# breakout.net
KiCad netlist of a schematic drawn in EAGLE
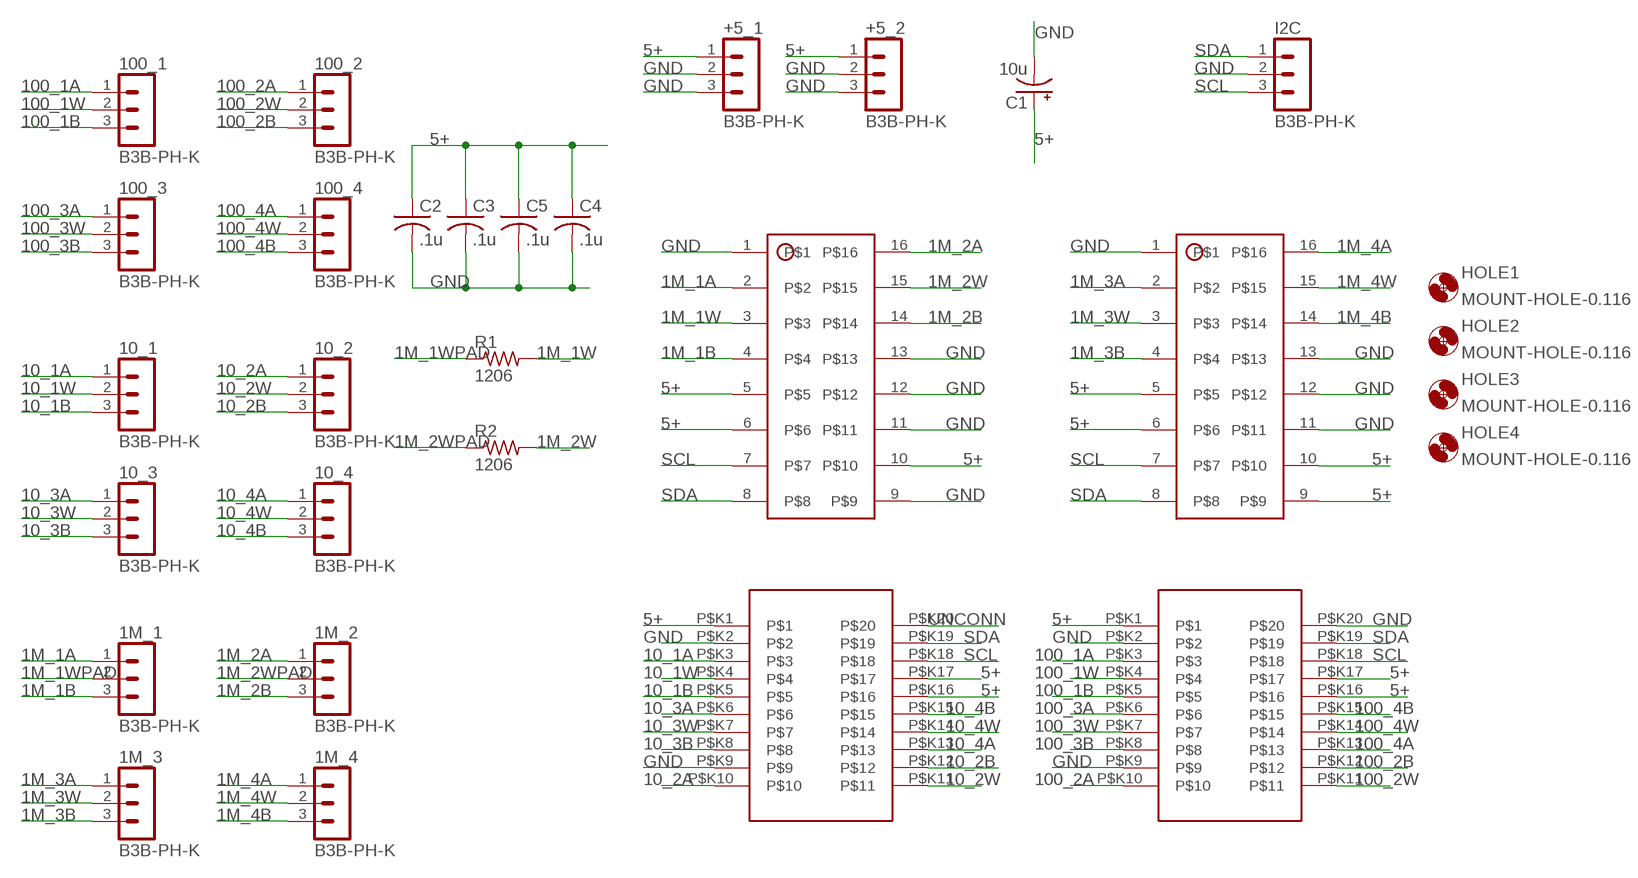
[diagram p0: schematic, sheet 1]

(export (version "E")
  (design (tool "Eeschema 10.0.6"))
  (components
    (comp (ref "+5_1")
      (value "B3B-PH-K")
      (footprint "eagle-import:B3B-PH-K")
      (libsource (lib "eagle-import") (part "B3B-PH-K"))
    )
    (comp (ref "+5_2")
      (value "B3B-PH-K")
      (footprint "eagle-import:B3B-PH-K")
      (libsource (lib "eagle-import") (part "B3B-PH-K"))
    )
    (comp (ref "1M_1")
      (value "B3B-PH-K")
      (footprint "eagle-import:B3B-PH-K")
      (libsource (lib "eagle-import") (part "B3B-PH-K"))
    )
    (comp (ref "1M_2")
      (value "B3B-PH-K")
      (footprint "eagle-import:B3B-PH-K")
      (libsource (lib "eagle-import") (part "B3B-PH-K"))
    )
    (comp (ref "1M_3")
      (value "B3B-PH-K")
      (footprint "eagle-import:B3B-PH-K")
      (libsource (lib "eagle-import") (part "B3B-PH-K"))
    )
    (comp (ref "1M_4")
      (value "B3B-PH-K")
      (footprint "eagle-import:B3B-PH-K")
      (libsource (lib "eagle-import") (part "B3B-PH-K"))
    )
    (comp (ref "10K")
      (value "TSSOP20")
      (footprint "eagle-import:TSSOP20")
      (libsource (lib "eagle-import") (part "TSSOP20"))
    )
    (comp (ref "10_1")
      (value "B3B-PH-K")
      (footprint "eagle-import:B3B-PH-K")
      (libsource (lib "eagle-import") (part "B3B-PH-K"))
    )
    (comp (ref "10_2")
      (value "B3B-PH-K")
      (footprint "eagle-import:B3B-PH-K")
      (libsource (lib "eagle-import") (part "B3B-PH-K"))
    )
    (comp (ref "10_3")
      (value "B3B-PH-K")
      (footprint "eagle-import:B3B-PH-K")
      (libsource (lib "eagle-import") (part "B3B-PH-K"))
    )
    (comp (ref "10_4")
      (value "B3B-PH-K")
      (footprint "eagle-import:B3B-PH-K")
      (libsource (lib "eagle-import") (part "B3B-PH-K"))
    )
    (comp (ref "100K")
      (value "TSSOP20")
      (footprint "eagle-import:TSSOP20")
      (libsource (lib "eagle-import") (part "TSSOP20"))
    )
    (comp (ref "100_1")
      (value "B3B-PH-K")
      (footprint "eagle-import:B3B-PH-K")
      (libsource (lib "eagle-import") (part "B3B-PH-K"))
    )
    (comp (ref "100_2")
      (value "B3B-PH-K")
      (footprint "eagle-import:B3B-PH-K")
      (libsource (lib "eagle-import") (part "B3B-PH-K"))
    )
    (comp (ref "100_3")
      (value "B3B-PH-K")
      (footprint "eagle-import:B3B-PH-K")
      (libsource (lib "eagle-import") (part "B3B-PH-K"))
    )
    (comp (ref "100_4")
      (value "B3B-PH-K")
      (footprint "eagle-import:B3B-PH-K")
      (libsource (lib "eagle-import") (part "B3B-PH-K"))
    )
    (comp (ref "C1")
      (value "10u")
      (footprint "eagle-import:E3,5-8")
      (libsource (lib "eagle-import") (part "CPOL-USE3.5-8"))
    )
    (comp (ref "C2")
      (value ".1u")
      (footprint "eagle-import:C1206K")
      (libsource (lib "eagle-import") (part "C-USC1206K"))
    )
    (comp (ref "C3")
      (value ".1u")
      (footprint "eagle-import:C1206K")
      (libsource (lib "eagle-import") (part "C-USC1206K"))
    )
    (comp (ref "C4")
      (value ".1u")
      (footprint "eagle-import:C1206K")
      (libsource (lib "eagle-import") (part "C-USC1206K"))
    )
    (comp (ref "C5")
      (value ".1u")
      (footprint "eagle-import:C1206K")
      (libsource (lib "eagle-import") (part "C-USC1206K"))
    )
    (comp (ref "HOLE1")
      (value "MOUNT-HOLE-0.116")
      (footprint "eagle-import:116")
      (libsource (lib "eagle-import") (part "MOUNT-HOLE-0.116"))
    )
    (comp (ref "HOLE2")
      (value "MOUNT-HOLE-0.116")
      (footprint "eagle-import:116")
      (libsource (lib "eagle-import") (part "MOUNT-HOLE-0.116"))
    )
    (comp (ref "HOLE3")
      (value "MOUNT-HOLE-0.116")
      (footprint "eagle-import:116")
      (libsource (lib "eagle-import") (part "MOUNT-HOLE-0.116"))
    )
    (comp (ref "HOLE4")
      (value "MOUNT-HOLE-0.116")
      (footprint "eagle-import:116")
      (libsource (lib "eagle-import") (part "MOUNT-HOLE-0.116"))
    )
    (comp (ref "I2C")
      (value "B3B-PH-K")
      (footprint "eagle-import:B3B-PH-K")
      (libsource (lib "eagle-import") (part "B3B-PH-K"))
    )
    (comp (ref "MEG_1")
      (value "SOIC-16")
      (footprint "eagle-import:SOIC127P600X175-16N")
      (libsource (lib "eagle-import") (part "SOIC-16"))
    )
    (comp (ref "MEG_2")
      (value "SOIC-16")
      (footprint "eagle-import:SOIC127P600X175-16N")
      (libsource (lib "eagle-import") (part "SOIC-16"))
    )
    (comp (ref "R1")
      (value "1206")
      (footprint "eagle-import:R1206")
      (libsource (lib "eagle-import") (part "R-US_R1206"))
    )
    (comp (ref "R2")
      (value "1206")
      (footprint "eagle-import:R1206")
      (libsource (lib "eagle-import") (part "R-US_R1206"))
    )
  )
  (nets
    (net (code "1") (name "/1M_1A") (class "Default")
      (node (ref "1M_1") (pin "1") (pinfunction "1_1") (pintype "passive"))
      (node (ref "MEG_1") (pin "2") (pinfunction "P$2_2") (pintype "bidirectional"))
    )
    (net (code "2") (name "/1M_1B") (class "Default")
      (node (ref "1M_1") (pin "3") (pinfunction "3_3") (pintype "passive"))
      (node (ref "MEG_1") (pin "4") (pinfunction "P$4_4") (pintype "bidirectional"))
    )
    (net (code "3") (name "/1M_1W") (class "Default")
      (node (ref "MEG_1") (pin "3") (pinfunction "P$3_3") (pintype "bidirectional"))
      (node (ref "R1") (pin "2") (pinfunction "2_2") (pintype "passive"))
    )
    (net (code "4") (name "/1M_1WPAD") (class "Default")
      (node (ref "1M_1") (pin "2") (pinfunction "2_2") (pintype "passive"))
      (node (ref "R1") (pin "1") (pinfunction "1_1") (pintype "passive"))
    )
    (net (code "5") (name "/1M_2A") (class "Default")
      (node (ref "1M_2") (pin "1") (pinfunction "1_1") (pintype "passive"))
      (node (ref "MEG_1") (pin "16") (pinfunction "P$16_16") (pintype "bidirectional"))
    )
    (net (code "6") (name "/1M_2B") (class "Default")
      (node (ref "1M_2") (pin "3") (pinfunction "3_3") (pintype "passive"))
      (node (ref "MEG_1") (pin "14") (pinfunction "P$14_14") (pintype "bidirectional"))
    )
    (net (code "7") (name "/1M_2W") (class "Default")
      (node (ref "MEG_1") (pin "15") (pinfunction "P$15_15") (pintype "bidirectional"))
      (node (ref "R2") (pin "2") (pinfunction "2_2") (pintype "passive"))
    )
    (net (code "8") (name "/1M_2WPAD") (class "Default")
      (node (ref "1M_2") (pin "2") (pinfunction "2_2") (pintype "passive"))
      (node (ref "R2") (pin "1") (pinfunction "1_1") (pintype "passive"))
    )
    (net (code "9") (name "/1M_3A") (class "Default")
      (node (ref "1M_3") (pin "1") (pinfunction "1_1") (pintype "passive"))
      (node (ref "MEG_2") (pin "2") (pinfunction "P$2_2") (pintype "bidirectional"))
    )
    (net (code "10") (name "/1M_3B") (class "Default")
      (node (ref "1M_3") (pin "3") (pinfunction "3_3") (pintype "passive"))
      (node (ref "MEG_2") (pin "4") (pinfunction "P$4_4") (pintype "bidirectional"))
    )
    (net (code "11") (name "/1M_3W") (class "Default")
      (node (ref "1M_3") (pin "2") (pinfunction "2_2") (pintype "passive"))
      (node (ref "MEG_2") (pin "3") (pinfunction "P$3_3") (pintype "bidirectional"))
    )
    (net (code "12") (name "/1M_4A") (class "Default")
      (node (ref "1M_4") (pin "1") (pinfunction "1_1") (pintype "passive"))
      (node (ref "MEG_2") (pin "16") (pinfunction "P$16_16") (pintype "bidirectional"))
    )
    (net (code "13") (name "/1M_4B") (class "Default")
      (node (ref "1M_4") (pin "3") (pinfunction "3_3") (pintype "passive"))
      (node (ref "MEG_2") (pin "14") (pinfunction "P$14_14") (pintype "bidirectional"))
    )
    (net (code "14") (name "/1M_4W") (class "Default")
      (node (ref "1M_4") (pin "2") (pinfunction "2_2") (pintype "passive"))
      (node (ref "MEG_2") (pin "15") (pinfunction "P$15_15") (pintype "bidirectional"))
    )
    (net (code "15") (name "/5+") (class "Default")
      (node (ref "+5_1") (pin "1") (pinfunction "1_1") (pintype "passive"))
      (node (ref "+5_2") (pin "1") (pinfunction "1_1") (pintype "passive"))
      (node (ref "100K") (pin "P$K1") (pinfunction "P$1_P$K1") (pintype "bidirectional"))
      (node (ref "100K") (pin "P$K16") (pinfunction "P$16_P$K16") (pintype "bidirectional"))
      (node (ref "100K") (pin "P$K17") (pinfunction "P$17_P$K17") (pintype "bidirectional"))
      (node (ref "10K") (pin "P$K1") (pinfunction "P$1_P$K1") (pintype "bidirectional"))
      (node (ref "10K") (pin "P$K16") (pinfunction "P$16_P$K16") (pintype "bidirectional"))
      (node (ref "10K") (pin "P$K17") (pinfunction "P$17_P$K17") (pintype "bidirectional"))
      (node (ref "C1") (pin "+") (pinfunction "+_+") (pintype "passive"))
      (node (ref "C2") (pin "1") (pinfunction "1_1") (pintype "passive"))
      (node (ref "C3") (pin "1") (pinfunction "1_1") (pintype "passive"))
      (node (ref "C4") (pin "1") (pinfunction "1_1") (pintype "passive"))
      (node (ref "C5") (pin "1") (pinfunction "1_1") (pintype "passive"))
      (node (ref "MEG_1") (pin "10") (pinfunction "P$10_10") (pintype "bidirectional"))
      (node (ref "MEG_1") (pin "5") (pinfunction "P$5_5") (pintype "bidirectional"))
      (node (ref "MEG_1") (pin "6") (pinfunction "P$6_6") (pintype "bidirectional"))
      (node (ref "MEG_2") (pin "10") (pinfunction "P$10_10") (pintype "bidirectional"))
      (node (ref "MEG_2") (pin "5") (pinfunction "P$5_5") (pintype "bidirectional"))
      (node (ref "MEG_2") (pin "6") (pinfunction "P$6_6") (pintype "bidirectional"))
      (node (ref "MEG_2") (pin "9") (pinfunction "P$9_9") (pintype "bidirectional"))
    )
    (net (code "16") (name "/10_1A") (class "Default")
      (node (ref "10K") (pin "P$K3") (pinfunction "P$3_P$K3") (pintype "bidirectional"))
      (node (ref "10_1") (pin "1") (pinfunction "1_1") (pintype "passive"))
    )
    (net (code "17") (name "/10_1B") (class "Default")
      (node (ref "10K") (pin "P$K5") (pinfunction "P$5_P$K5") (pintype "bidirectional"))
      (node (ref "10_1") (pin "3") (pinfunction "3_3") (pintype "passive"))
    )
    (net (code "18") (name "/10_1W") (class "Default")
      (node (ref "10K") (pin "P$K4") (pinfunction "P$4_P$K4") (pintype "bidirectional"))
      (node (ref "10_1") (pin "2") (pinfunction "2_2") (pintype "passive"))
    )
    (net (code "19") (name "/10_2A") (class "Default")
      (node (ref "10K") (pin "P$K10") (pinfunction "P$10_P$K10") (pintype "bidirectional"))
      (node (ref "10_2") (pin "1") (pinfunction "1_1") (pintype "passive"))
    )
    (net (code "20") (name "/10_2B") (class "Default")
      (node (ref "10K") (pin "P$K12") (pinfunction "P$12_P$K12") (pintype "bidirectional"))
      (node (ref "10_2") (pin "3") (pinfunction "3_3") (pintype "passive"))
    )
    (net (code "21") (name "/10_2W") (class "Default")
      (node (ref "10K") (pin "P$K11") (pinfunction "P$11_P$K11") (pintype "bidirectional"))
      (node (ref "10_2") (pin "2") (pinfunction "2_2") (pintype "passive"))
    )
    (net (code "22") (name "/10_3A") (class "Default")
      (node (ref "10K") (pin "P$K6") (pinfunction "P$6_P$K6") (pintype "bidirectional"))
      (node (ref "10_3") (pin "1") (pinfunction "1_1") (pintype "passive"))
    )
    (net (code "23") (name "/10_3B") (class "Default")
      (node (ref "10K") (pin "P$K8") (pinfunction "P$8_P$K8") (pintype "bidirectional"))
      (node (ref "10_3") (pin "3") (pinfunction "3_3") (pintype "passive"))
    )
    (net (code "24") (name "/10_3W") (class "Default")
      (node (ref "10K") (pin "P$K7") (pinfunction "P$7_P$K7") (pintype "bidirectional"))
      (node (ref "10_3") (pin "2") (pinfunction "2_2") (pintype "passive"))
    )
    (net (code "25") (name "/10_4A") (class "Default")
      (node (ref "10K") (pin "P$K13") (pinfunction "P$13_P$K13") (pintype "bidirectional"))
      (node (ref "10_4") (pin "1") (pinfunction "1_1") (pintype "passive"))
    )
    (net (code "26") (name "/10_4B") (class "Default")
      (node (ref "10K") (pin "P$K15") (pinfunction "P$15_P$K15") (pintype "bidirectional"))
      (node (ref "10_4") (pin "3") (pinfunction "3_3") (pintype "passive"))
    )
    (net (code "27") (name "/10_4W") (class "Default")
      (node (ref "10K") (pin "P$K14") (pinfunction "P$14_P$K14") (pintype "bidirectional"))
      (node (ref "10_4") (pin "2") (pinfunction "2_2") (pintype "passive"))
    )
    (net (code "28") (name "/100_1A") (class "Default")
      (node (ref "100K") (pin "P$K3") (pinfunction "P$3_P$K3") (pintype "bidirectional"))
      (node (ref "100_1") (pin "1") (pinfunction "1_1") (pintype "passive"))
    )
    (net (code "29") (name "/100_1B") (class "Default")
      (node (ref "100K") (pin "P$K5") (pinfunction "P$5_P$K5") (pintype "bidirectional"))
      (node (ref "100_1") (pin "3") (pinfunction "3_3") (pintype "passive"))
    )
    (net (code "30") (name "/100_1W") (class "Default")
      (node (ref "100K") (pin "P$K4") (pinfunction "P$4_P$K4") (pintype "bidirectional"))
      (node (ref "100_1") (pin "2") (pinfunction "2_2") (pintype "passive"))
    )
    (net (code "31") (name "/100_2A") (class "Default")
      (node (ref "100K") (pin "P$K10") (pinfunction "P$10_P$K10") (pintype "bidirectional"))
      (node (ref "100_2") (pin "1") (pinfunction "1_1") (pintype "passive"))
    )
    (net (code "32") (name "/100_2B") (class "Default")
      (node (ref "100K") (pin "P$K12") (pinfunction "P$12_P$K12") (pintype "bidirectional"))
      (node (ref "100_2") (pin "3") (pinfunction "3_3") (pintype "passive"))
    )
    (net (code "33") (name "/100_2W") (class "Default")
      (node (ref "100K") (pin "P$K11") (pinfunction "P$11_P$K11") (pintype "bidirectional"))
      (node (ref "100_2") (pin "2") (pinfunction "2_2") (pintype "passive"))
    )
    (net (code "34") (name "/100_3A") (class "Default")
      (node (ref "100K") (pin "P$K6") (pinfunction "P$6_P$K6") (pintype "bidirectional"))
      (node (ref "100_3") (pin "1") (pinfunction "1_1") (pintype "passive"))
    )
    (net (code "35") (name "/100_3B") (class "Default")
      (node (ref "100K") (pin "P$K8") (pinfunction "P$8_P$K8") (pintype "bidirectional"))
      (node (ref "100_3") (pin "3") (pinfunction "3_3") (pintype "passive"))
    )
    (net (code "36") (name "/100_3W") (class "Default")
      (node (ref "100K") (pin "P$K7") (pinfunction "P$7_P$K7") (pintype "bidirectional"))
      (node (ref "100_3") (pin "2") (pinfunction "2_2") (pintype "passive"))
    )
    (net (code "37") (name "/100_4A") (class "Default")
      (node (ref "100K") (pin "P$K13") (pinfunction "P$13_P$K13") (pintype "bidirectional"))
      (node (ref "100_4") (pin "1") (pinfunction "1_1") (pintype "passive"))
    )
    (net (code "38") (name "/100_4B") (class "Default")
      (node (ref "100K") (pin "P$K15") (pinfunction "P$15_P$K15") (pintype "bidirectional"))
      (node (ref "100_4") (pin "3") (pinfunction "3_3") (pintype "passive"))
    )
    (net (code "39") (name "/100_4W") (class "Default")
      (node (ref "100K") (pin "P$K14") (pinfunction "P$14_P$K14") (pintype "bidirectional"))
      (node (ref "100_4") (pin "2") (pinfunction "2_2") (pintype "passive"))
    )
    (net (code "40") (name "/GND") (class "Default")
      (node (ref "+5_1") (pin "2") (pinfunction "2_2") (pintype "passive"))
      (node (ref "+5_1") (pin "3") (pinfunction "3_3") (pintype "passive"))
      (node (ref "+5_2") (pin "2") (pinfunction "2_2") (pintype "passive"))
      (node (ref "+5_2") (pin "3") (pinfunction "3_3") (pintype "passive"))
      (node (ref "100K") (pin "P$K2") (pinfunction "P$2_P$K2") (pintype "bidirectional"))
      (node (ref "100K") (pin "P$K20") (pinfunction "P$20_P$K20") (pintype "bidirectional"))
      (node (ref "100K") (pin "P$K9") (pinfunction "P$9_P$K9") (pintype "bidirectional"))
      (node (ref "10K") (pin "P$K2") (pinfunction "P$2_P$K2") (pintype "bidirectional"))
      (node (ref "10K") (pin "P$K9") (pinfunction "P$9_P$K9") (pintype "bidirectional"))
      (node (ref "C1") (pin "-") (pinfunction "-_-") (pintype "passive"))
      (node (ref "C2") (pin "2") (pinfunction "2_2") (pintype "passive"))
      (node (ref "C3") (pin "2") (pinfunction "2_2") (pintype "passive"))
      (node (ref "C4") (pin "2") (pinfunction "2_2") (pintype "passive"))
      (node (ref "C5") (pin "2") (pinfunction "2_2") (pintype "passive"))
      (node (ref "I2C") (pin "2") (pinfunction "2_2") (pintype "passive"))
      (node (ref "MEG_1") (pin "1") (pinfunction "P$1_1") (pintype "bidirectional"))
      (node (ref "MEG_1") (pin "11") (pinfunction "P$11_11") (pintype "bidirectional"))
      (node (ref "MEG_1") (pin "12") (pinfunction "P$12_12") (pintype "bidirectional"))
      (node (ref "MEG_1") (pin "13") (pinfunction "P$13_13") (pintype "bidirectional"))
      (node (ref "MEG_1") (pin "9") (pinfunction "P$9_9") (pintype "bidirectional"))
      (node (ref "MEG_2") (pin "1") (pinfunction "P$1_1") (pintype "bidirectional"))
      (node (ref "MEG_2") (pin "11") (pinfunction "P$11_11") (pintype "bidirectional"))
      (node (ref "MEG_2") (pin "12") (pinfunction "P$12_12") (pintype "bidirectional"))
      (node (ref "MEG_2") (pin "13") (pinfunction "P$13_13") (pintype "bidirectional"))
    )
    (net (code "41") (name "/SCL") (class "Default")
      (node (ref "100K") (pin "P$K18") (pinfunction "P$18_P$K18") (pintype "bidirectional"))
      (node (ref "10K") (pin "P$K18") (pinfunction "P$18_P$K18") (pintype "bidirectional"))
      (node (ref "I2C") (pin "3") (pinfunction "3_3") (pintype "passive"))
      (node (ref "MEG_1") (pin "7") (pinfunction "P$7_7") (pintype "bidirectional"))
      (node (ref "MEG_2") (pin "7") (pinfunction "P$7_7") (pintype "bidirectional"))
    )
    (net (code "42") (name "/SDA") (class "Default")
      (node (ref "100K") (pin "P$K19") (pinfunction "P$19_P$K19") (pintype "bidirectional"))
      (node (ref "10K") (pin "P$K19") (pinfunction "P$19_P$K19") (pintype "bidirectional"))
      (node (ref "I2C") (pin "1") (pinfunction "1_1") (pintype "passive"))
      (node (ref "MEG_1") (pin "8") (pinfunction "P$8_8") (pintype "bidirectional"))
      (node (ref "MEG_2") (pin "8") (pinfunction "P$8_8") (pintype "bidirectional"))
    )
    (net (code "43") (name "/UNCONN") (class "Default")
      (node (ref "10K") (pin "P$K20") (pinfunction "P$20_P$K20") (pintype "bidirectional"))
    )
  )
)
